# GPRSshield_V2.net
KiCad netlist of a schematic drawn in EAGLE
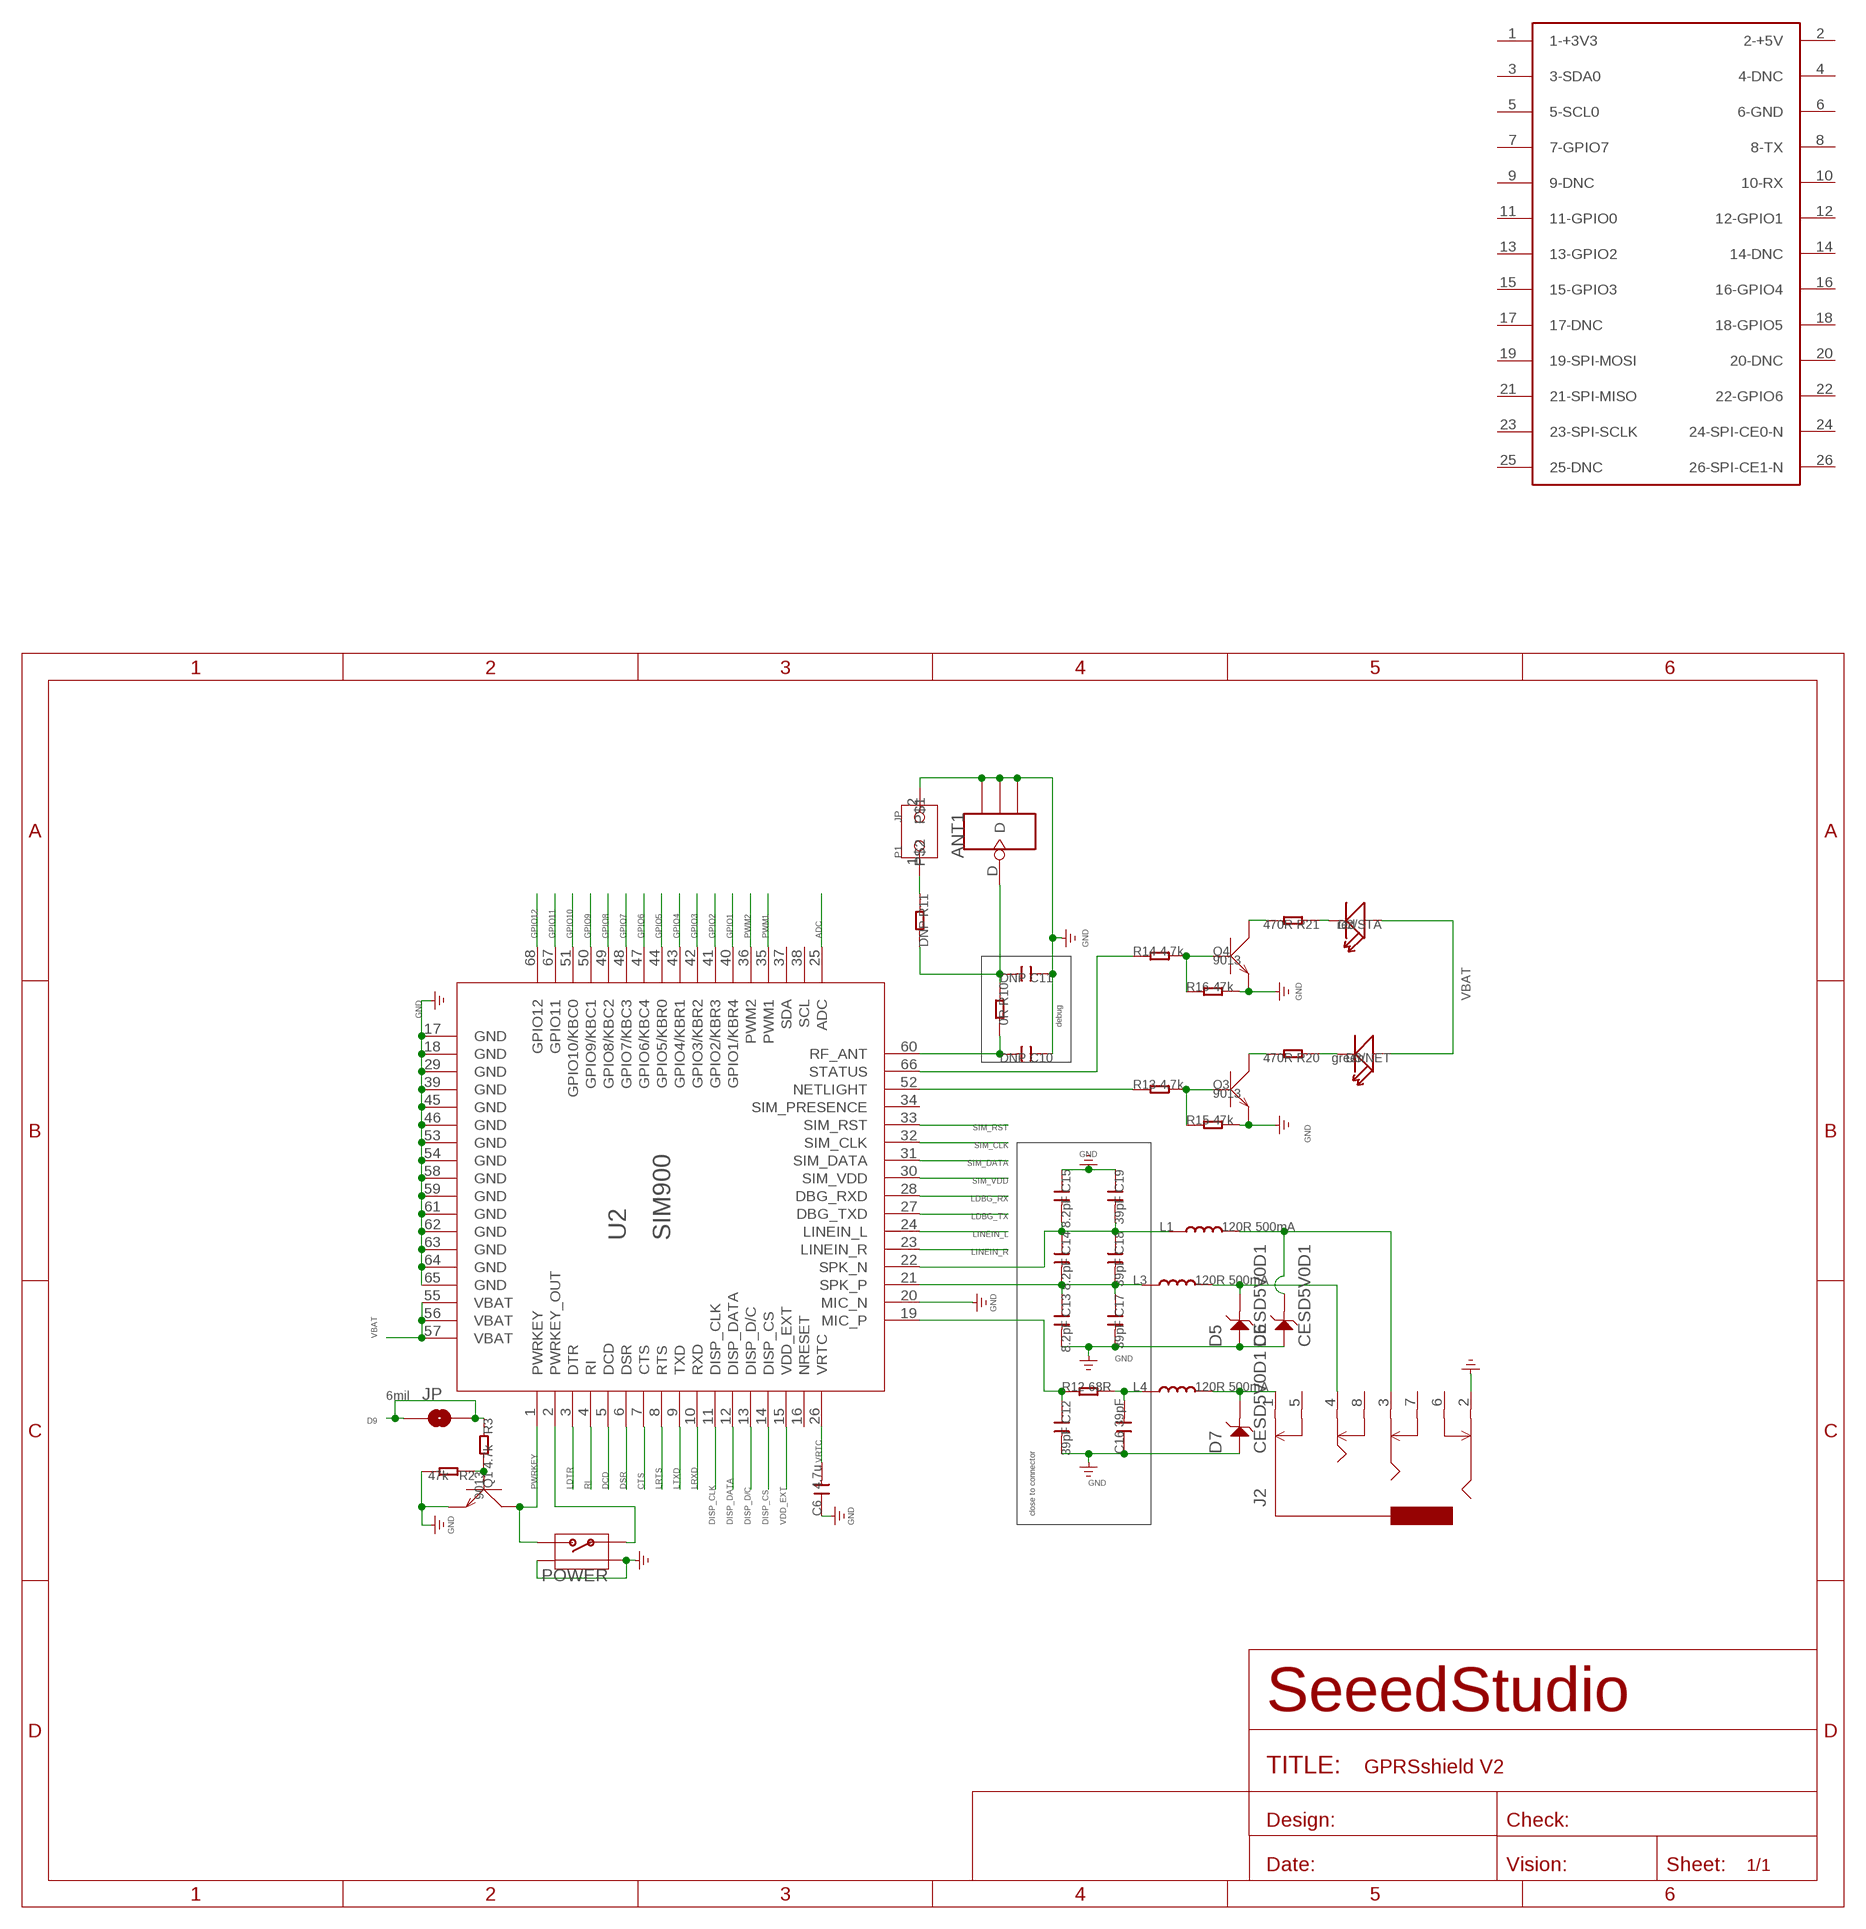
[diagram p0: schematic, sheet 1, part 1 of 2]
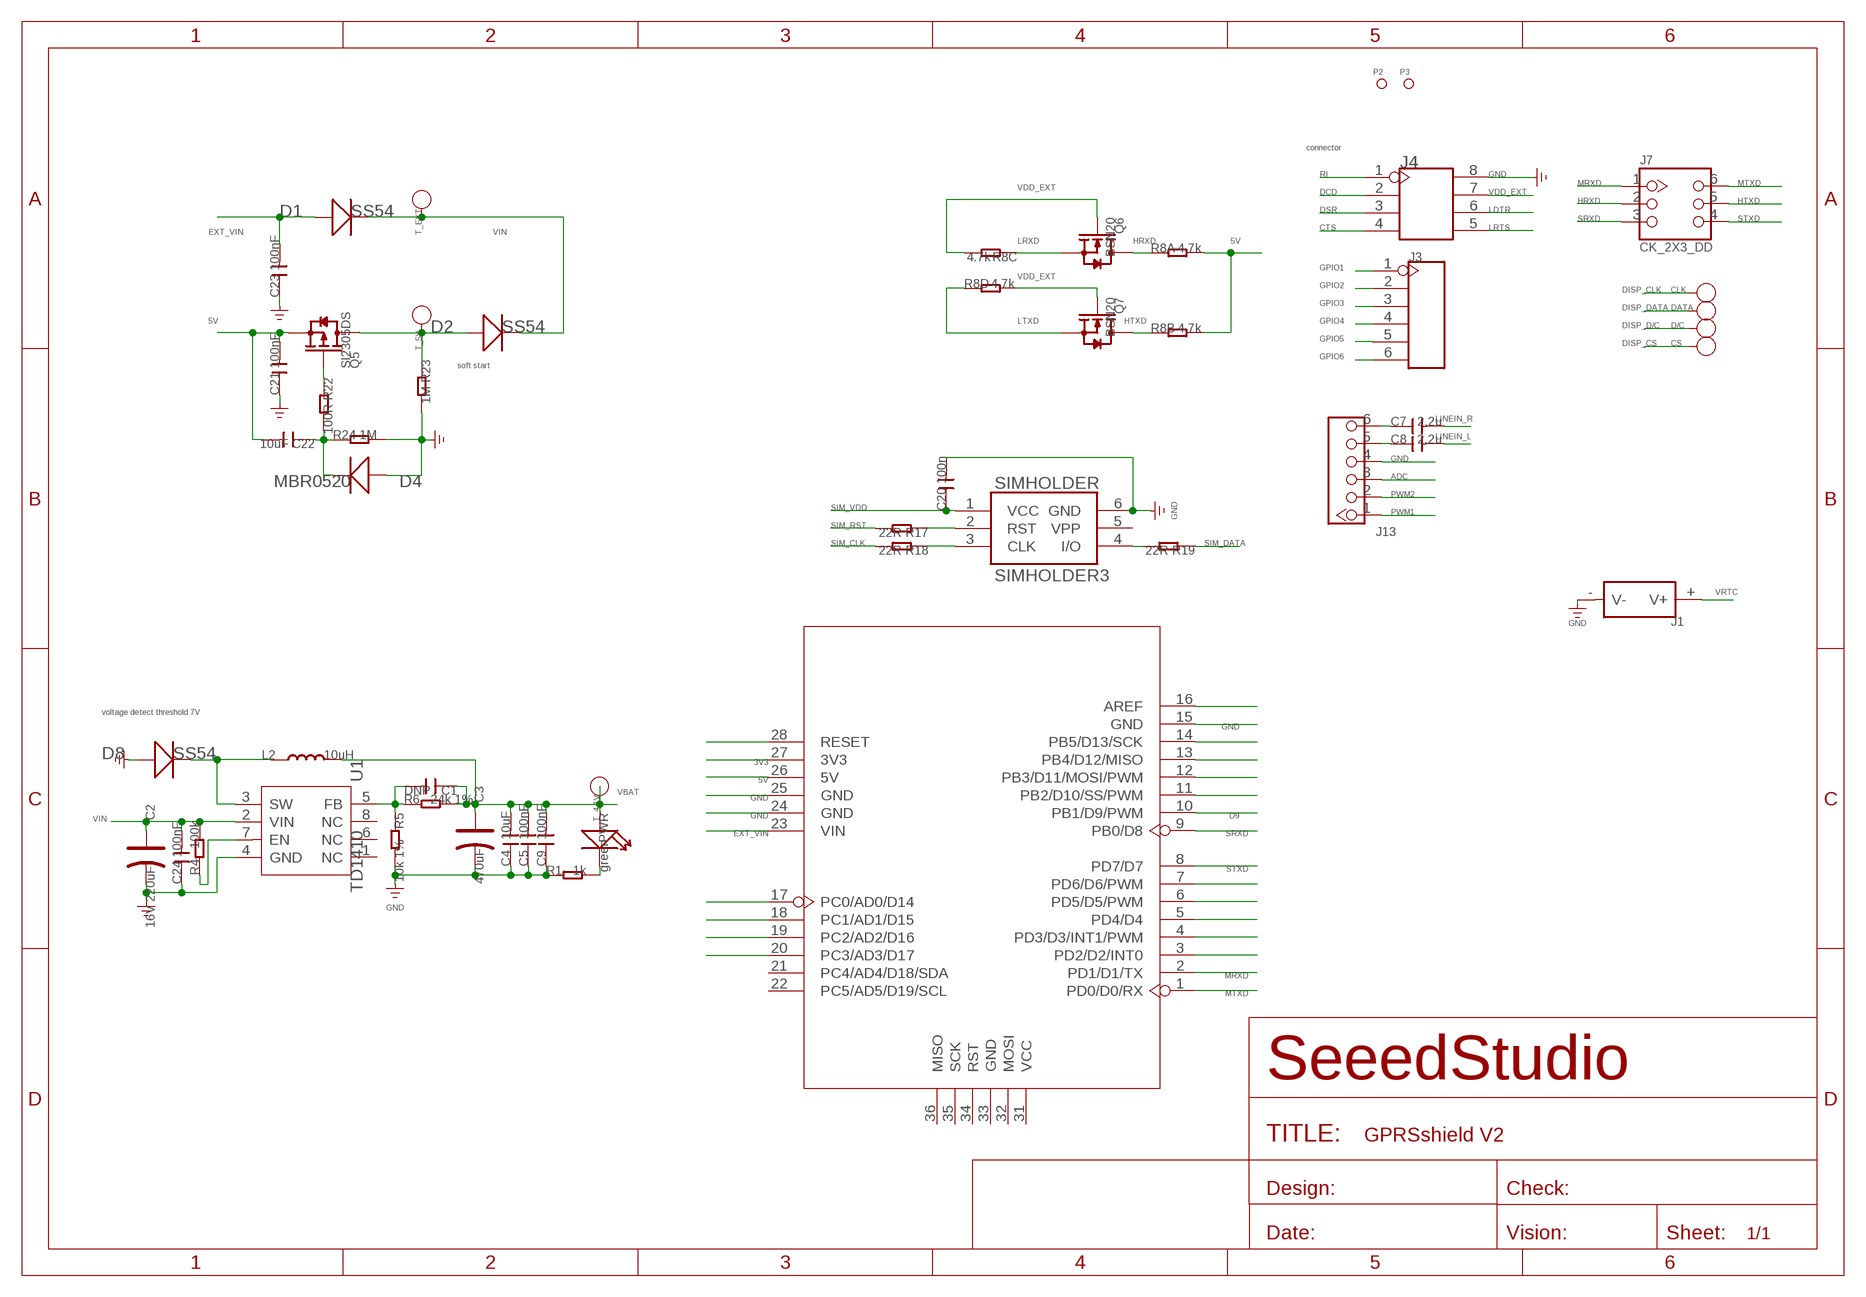
[diagram p1: schematic, sheet 1, part 2 of 2]

(export (version "E")
  (design (tool "Eeschema 10.0.6"))
  (components
    (comp (ref "ANT1")
      (value "ANTENNA-U-FL")
      (footprint "eagle-import:4P-U-FL")
      (libsource (lib "eagle-import") (part "ANTENNA-U-FL"))
    )
    (comp (ref "C1")
      (value "DNP")
      (footprint "eagle-import:C0603")
      (libsource (lib "eagle-import") (part "C-0603"))
    )
    (comp (ref "C2")
      (value "16V 220uF")
      (footprint "eagle-import:ELECTRO-SMD-D-5.6MM")
      (libsource (lib "eagle-import") (part "CAP-ELECTRO-D"))
    )
    (comp (ref "C3")
      (value "470uF")
      (footprint "eagle-import:AVX-D")
      (libsource (lib "eagle-import") (part "CAP-AVX-D"))
    )
    (comp (ref "C4")
      (value "10uF")
      (footprint "eagle-import:C0805")
      (libsource (lib "eagle-import") (part "C-0805"))
    )
    (comp (ref "C5")
      (value "100nF")
      (footprint "eagle-import:C0603")
      (libsource (lib "eagle-import") (part "C-0603"))
    )
    (comp (ref "C6")
      (value "4.7u")
      (footprint "eagle-import:C0805")
      (libsource (lib "eagle-import") (part "C-0805"))
    )
    (comp (ref "C7")
      (value "2.2u")
      (footprint "eagle-import:C0805")
      (libsource (lib "eagle-import") (part "C-0805"))
    )
    (comp (ref "C8")
      (value "2.2u")
      (footprint "eagle-import:C0805")
      (libsource (lib "eagle-import") (part "C-0805"))
    )
    (comp (ref "C9")
      (value "100nF")
      (footprint "eagle-import:C0603")
      (libsource (lib "eagle-import") (part "C-0603"))
    )
    (comp (ref "C10")
      (value "DNP")
      (footprint "eagle-import:C0603")
      (libsource (lib "eagle-import") (part "C-0603"))
    )
    (comp (ref "C11")
      (value "DNP")
      (footprint "eagle-import:C0603")
      (libsource (lib "eagle-import") (part "C-0603"))
    )
    (comp (ref "C12")
      (value "39pF")
      (footprint "eagle-import:C0603")
      (libsource (lib "eagle-import") (part "C-0603"))
    )
    (comp (ref "C13")
      (value "8.2pF")
      (footprint "eagle-import:C0603")
      (libsource (lib "eagle-import") (part "C-0603"))
    )
    (comp (ref "C14")
      (value "8.2pF")
      (footprint "eagle-import:C0603")
      (libsource (lib "eagle-import") (part "C-0603"))
    )
    (comp (ref "C15")
      (value "8.2pF")
      (footprint "eagle-import:C0603")
      (libsource (lib "eagle-import") (part "C-0603"))
    )
    (comp (ref "C16")
      (value "39pF")
      (footprint "eagle-import:C0603")
      (libsource (lib "eagle-import") (part "C-0603"))
    )
    (comp (ref "C17")
      (value "39pF")
      (footprint "eagle-import:C0603")
      (libsource (lib "eagle-import") (part "C-0603"))
    )
    (comp (ref "C18")
      (value "39pF")
      (footprint "eagle-import:C0603")
      (libsource (lib "eagle-import") (part "C-0603"))
    )
    (comp (ref "C19")
      (value "39pF")
      (footprint "eagle-import:C0603")
      (libsource (lib "eagle-import") (part "C-0603"))
    )
    (comp (ref "C20")
      (value "100n")
      (footprint "eagle-import:C0603")
      (libsource (lib "eagle-import") (part "C-0603"))
    )
    (comp (ref "C21")
      (value "100nF")
      (footprint "eagle-import:C0603")
      (libsource (lib "eagle-import") (part "C-0603"))
    )
    (comp (ref "C22")
      (value "10uF")
      (footprint "eagle-import:C0805")
      (libsource (lib "eagle-import") (part "C-0805"))
    )
    (comp (ref "C23")
      (value "100nF")
      (footprint "eagle-import:C0603")
      (libsource (lib "eagle-import") (part "C-0603"))
    )
    (comp (ref "C24")
      (value "100nF")
      (footprint "eagle-import:C0603")
      (libsource (lib "eagle-import") (part "C-0603"))
    )
    (comp (ref "CLK")
      (value "PAD-TEST-POINT-CIRCLE'4545'")
      (footprint "eagle-import:TP_4545")
      (fields (field (name "PARTNO") "DNP"))
      (libsource (lib "eagle-import") (part "PAD-TEST-POINT-CIRCLE'4545'"))
    )
    (comp (ref "CS")
      (value "PAD-TEST-POINT-CIRCLE'4545'")
      (footprint "eagle-import:TP_4545")
      (fields (field (name "PARTNO") "DNP"))
      (libsource (lib "eagle-import") (part "PAD-TEST-POINT-CIRCLE'4545'"))
    )
    (comp (ref "D/C")
      (value "PAD-TEST-POINT-CIRCLE'4545'")
      (footprint "eagle-import:TP_4545")
      (fields (field (name "PARTNO") "DNP"))
      (libsource (lib "eagle-import") (part "PAD-TEST-POINT-CIRCLE'4545'"))
    )
    (comp (ref "D1")
      (value "SS54")
      (footprint "eagle-import:SMB")
      (libsource (lib "eagle-import") (part "D'MBRS240LT3'"))
    )
    (comp (ref "D2")
      (value "SS54")
      (footprint "eagle-import:SMB")
      (libsource (lib "eagle-import") (part "D'MBRS240LT3'"))
    )
    (comp (ref "D2/STA")
      (value "red")
      (footprint "eagle-import:LED-0603")
      (libsource (lib "eagle-import") (part "LED'0603'"))
    )
    (comp (ref "D3/NET")
      (value "green")
      (footprint "eagle-import:LED-0603")
      (libsource (lib "eagle-import") (part "LED'0603'"))
    )
    (comp (ref "D4")
      (value "MBR0520")
      (footprint "eagle-import:SOD123-2.7X1.6")
      (libsource (lib "eagle-import") (part "D'MBR0520LT1'"))
    )
    (comp (ref "D5")
      (value "CESD5V0D1")
      (footprint "eagle-import:SOD123-2.7X1.6")
      (libsource (lib "eagle-import") (part "D-ESD"))
    )
    (comp (ref "D6")
      (value "CESD5V0D1")
      (footprint "eagle-import:SOD123-2.7X1.6")
      (libsource (lib "eagle-import") (part "D-ESD"))
    )
    (comp (ref "D7")
      (value "CESD5V0D1")
      (footprint "eagle-import:SOD123-2.7X1.6")
      (libsource (lib "eagle-import") (part "D-ESD"))
    )
    (comp (ref "D8")
      (value "SS54")
      (footprint "eagle-import:SMB")
      (libsource (lib "eagle-import") (part "D'MBRS240LT3'"))
    )
    (comp (ref "DATA")
      (value "PAD-TEST-POINT-CIRCLE'4545'")
      (footprint "eagle-import:TP_4545")
      (fields (field (name "PARTNO") "DNP"))
      (libsource (lib "eagle-import") (part "PAD-TEST-POINT-CIRCLE'4545'"))
    )
    (comp (ref "J1")
      (value "HOLDER-BAT")
      (footprint "eagle-import:SMD-CR1220-2")
      (libsource (lib "eagle-import") (part "HOLDER-BAT"))
    )
    (comp (ref "J2")
      (value "AUDIO-8P'PJ-3536-L6S'")
      (footprint "eagle-import:8P-3.5-SMD")
      (libsource (lib "eagle-import") (part "AUDIO-8P'PJ-3536-L6S'"))
    )
    (comp (ref "J3")
      (value "HEADER-6P-65/35MIL")
      (footprint "eagle-import:6P-2.54-65_35MIL")
      (libsource (lib "eagle-import") (part "HEADER-6P-65/35MIL"))
    )
    (comp (ref "J4")
      (value "HEADER-2X4P-2.54")
      (footprint "eagle-import:2X4P-2.54")
      (libsource (lib "eagle-import") (part "HEADER-2X4P-2.54"))
    )
    (comp (ref "J7")
      (value "CK_2X3_DD")
      (footprint "eagle-import:CK_2X3")
      (libsource (lib "eagle-import") (part "CK_2X3_DD"))
    )
    (comp (ref "J13")
      (value "HEADER_1X6")
      (footprint "eagle-import:CK_1X6")
      (libsource (lib "eagle-import") (part "HEADER_1X6"))
    )
    (comp (ref "JP")
      (value "PAD-SOLDERJUMPERNC")
      (footprint "eagle-import:2P-SMD-3.3X2")
      (libsource (lib "eagle-import") (part "PAD-SOLDERJUMPERNC"))
    )
    (comp (ref "L1")
      (value "120R 500mA")
      (footprint "eagle-import:L0603")
      (libsource (lib "eagle-import") (part "L'0603'"))
    )
    (comp (ref "L2")
      (value "10uH")
      (footprint "eagle-import:L0630")
      (libsource (lib "eagle-import") (part "L'0630'"))
    )
    (comp (ref "L3")
      (value "120R 500mA")
      (footprint "eagle-import:L0603")
      (libsource (lib "eagle-import") (part "L'0603'"))
    )
    (comp (ref "L4")
      (value "120R 500mA")
      (footprint "eagle-import:L0603")
      (libsource (lib "eagle-import") (part "L'0603'"))
    )
    (comp (ref "P1") (value "JP") (footprint "eagle-import:JP") (libsource (lib "eagle-import") (part "JP")))
    (comp (ref "P2")
      (value "PAD-MARK")
      (footprint "eagle-import:ROUND-MARK-1.0")
      (fields (field (name "PARTNO") "DNP"))
      (libsource (lib "eagle-import") (part "PAD-MARK"))
    )
    (comp (ref "P3")
      (value "PAD-MARK")
      (footprint "eagle-import:ROUND-MARK-1.0")
      (fields (field (name "PARTNO") "DNP"))
      (libsource (lib "eagle-import") (part "PAD-MARK"))
    )
    (comp (ref "POWER")
      (value "BUTTON-4P-REINFORCE'TS-118E'")
      (footprint "eagle-import:4P-SMD-7X3.5X3.5H")
      (libsource (lib "eagle-import") (part "BUTTON-4P-REINFORCE'TS-118E'"))
    )
    (comp (ref "PWR")
      (value "green")
      (footprint "eagle-import:D0603")
      (libsource (lib "eagle-import") (part "007-LED0603"))
    )
    (comp (ref "Q1")
      (value "9013")
      (footprint "eagle-import:SOT23")
      (libsource (lib "eagle-import") (part "TRANSISTOR-NPN-SOT23"))
    )
    (comp (ref "Q3")
      (value "9013")
      (footprint "eagle-import:SOT23")
      (libsource (lib "eagle-import") (part "TRANSISTOR-NPN-SOT23"))
    )
    (comp (ref "Q4")
      (value "9013")
      (footprint "eagle-import:SOT23")
      (libsource (lib "eagle-import") (part "TRANSISTOR-NPN-SOT23"))
    )
    (comp (ref "Q5")
      (value "SI2305DS")
      (footprint "eagle-import:SOT23")
      (libsource (lib "eagle-import") (part "MOSFET-P'SI2323CDS/SI2305DS{lt}BR{gt}'"))
    )
    (comp (ref "Q6")
      (value "BSN20")
      (footprint "eagle-import:SOT23")
      (libsource (lib "eagle-import") (part "MOSFET-N'SOT23'"))
    )
    (comp (ref "Q7")
      (value "BSN20")
      (footprint "eagle-import:SOT23")
      (libsource (lib "eagle-import") (part "MOSFET-N'SOT23'"))
    )
    (comp (ref "R1")
      (value "1k")
      (footprint "eagle-import:R0603")
      (libsource (lib "eagle-import") (part "R-0603"))
    )
    (comp (ref "R2")
      (value "47k")
      (footprint "eagle-import:R0603")
      (libsource (lib "eagle-import") (part "R-0603"))
    )
    (comp (ref "R3")
      (value "4.7k")
      (footprint "eagle-import:R0603")
      (libsource (lib "eagle-import") (part "R-0603"))
    )
    (comp (ref "R4")
      (value "100k")
      (footprint "eagle-import:R0603")
      (libsource (lib "eagle-import") (part "R-0603"))
    )
    (comp (ref "R5")
      (value "10k 1%")
      (footprint "eagle-import:R0603")
      (libsource (lib "eagle-import") (part "R-0603"))
    )
    (comp (ref "R6")
      (value "24k 1%")
      (footprint "eagle-import:R0603")
      (libsource (lib "eagle-import") (part "R-0603"))
    )
    (comp (ref "R8")
      (value "4.7k")
      (footprint "eagle-import:1206-8-3.3X2.4")
      (libsource (lib "eagle-import") (part "R-4R-1206"))
    )
    (comp (ref "R10")
      (value "0R")
      (footprint "eagle-import:R0603")
      (libsource (lib "eagle-import") (part "R-0603"))
    )
    (comp (ref "R11")
      (value "DNP")
      (footprint "eagle-import:R0603")
      (libsource (lib "eagle-import") (part "R-0603"))
    )
    (comp (ref "R12")
      (value "68R")
      (footprint "eagle-import:R0603")
      (libsource (lib "eagle-import") (part "R-0603"))
    )
    (comp (ref "R13")
      (value "4.7k")
      (footprint "eagle-import:R0603")
      (libsource (lib "eagle-import") (part "R-0603"))
    )
    (comp (ref "R14")
      (value "4.7k")
      (footprint "eagle-import:R0603")
      (libsource (lib "eagle-import") (part "R-0603"))
    )
    (comp (ref "R15")
      (value "47k")
      (footprint "eagle-import:R0603")
      (libsource (lib "eagle-import") (part "R-0603"))
    )
    (comp (ref "R16")
      (value "47k")
      (footprint "eagle-import:R0603")
      (libsource (lib "eagle-import") (part "R-0603"))
    )
    (comp (ref "R17")
      (value "22R")
      (footprint "eagle-import:R0603")
      (libsource (lib "eagle-import") (part "R-0603"))
    )
    (comp (ref "R18")
      (value "22R")
      (footprint "eagle-import:R0603")
      (libsource (lib "eagle-import") (part "R-0603"))
    )
    (comp (ref "R19")
      (value "22R")
      (footprint "eagle-import:R0603")
      (libsource (lib "eagle-import") (part "R-0603"))
    )
    (comp (ref "R20")
      (value "470R")
      (footprint "eagle-import:R0603")
      (libsource (lib "eagle-import") (part "R-0603"))
    )
    (comp (ref "R21")
      (value "470R")
      (footprint "eagle-import:R0603")
      (libsource (lib "eagle-import") (part "R-0603"))
    )
    (comp (ref "R22")
      (value "100R")
      (footprint "eagle-import:R0603")
      (libsource (lib "eagle-import") (part "R-0603"))
    )
    (comp (ref "R23")
      (value "1M")
      (footprint "eagle-import:R0603")
      (libsource (lib "eagle-import") (part "R-0603"))
    )
    (comp (ref "R24")
      (value "1M")
      (footprint "eagle-import:R0603")
      (libsource (lib "eagle-import") (part "R-0603"))
    )
    (comp (ref "SIMHOLDER")
      (value "SIMHOLDER3")
      (footprint "eagle-import:SIMHOLDER3")
      (libsource (lib "eagle-import") (part "SIMHOLDER3"))
    )
    (comp (ref "T_4.1V")
      (value "PAD-TEST-POINT-CIRCLE'4545'")
      (footprint "eagle-import:TP_4545")
      (fields (field (name "PARTNO") "DNP") (field (name "PARTNO_1") "DNP"))
      (libsource (lib "eagle-import") (part "PAD-TEST-POINT-CIRCLE'4545'"))
    )
    (comp (ref "T_5V")
      (value "PAD-TEST-POINT-CIRCLE'4545'")
      (footprint "eagle-import:TP_4545")
      (fields (field (name "PARTNO") "DNP") (field (name "PARTNO_1") "DNP"))
      (libsource (lib "eagle-import") (part "PAD-TEST-POINT-CIRCLE'4545'"))
    )
    (comp (ref "T_EXT")
      (value "PAD-TEST-POINT-CIRCLE'4545'")
      (footprint "eagle-import:TP_4545")
      (fields (field (name "PARTNO") "DNP") (field (name "PARTNO_1") "DNP"))
      (libsource (lib "eagle-import") (part "PAD-TEST-POINT-CIRCLE'4545'"))
    )
    (comp (ref "U$4")
      (value "RASPBERRY-PI")
      (footprint "eagle-import:RASPBERRY-PI")
      (libsource (lib "eagle-import") (part "RASPBERRY-PI"))
    )
    (comp (ref "U1")
      (value "TD1410")
      (footprint "eagle-import:SOP8")
      (libsource (lib "eagle-import") (part "TD1410"))
    )
    (comp (ref "U2")
      (value "SIM900")
      (footprint "eagle-import:SIM900")
      (libsource (lib "eagle-import") (part "SIM900"))
    )
    (comp (ref "U3")
      (value "ARDUINO'W/O-SILK'")
      (footprint "eagle-import:ARDUINO-W_O-SILK")
      (libsource (lib "eagle-import") (part "ARDUINO'W/O-SILK'"))
    )
  )
  (nets
    (net (code "1") (name "/3V3") (class "Default")
      (node (ref "U3") (pin "27") (pinfunction "3V3_27") (pintype "bidirectional"))
    )
    (net (code "2") (name "/5V") (class "Default")
      (node (ref "C21") (pin "2") (pinfunction "2_2") (pintype "passive"))
      (node (ref "C22") (pin "2") (pinfunction "2_2") (pintype "passive"))
      (node (ref "Q5") (pin "2") (pinfunction "S_2") (pintype "passive"))
      (node (ref "R8") (pin "7") (pinfunction "2_7") (pintype "passive"))
      (node (ref "R8") (pin "8") (pinfunction "2_8") (pintype "passive"))
      (node (ref "U3") (pin "26") (pinfunction "5V_26") (pintype "bidirectional"))
    )
    (net (code "3") (name "/ADC") (class "Default")
      (node (ref "J13") (pin "3") (pinfunction "3_3") (pintype "bidirectional"))
      (node (ref "U2") (pin "25") (pinfunction "ADC_25") (pintype "input"))
    )
    (net (code "4") (name "/CTS") (class "Default")
      (node (ref "J4") (pin "4") (pinfunction "4_4") (pintype "bidirectional"))
      (node (ref "U2") (pin "7") (pinfunction "CTS_7") (pintype "output"))
    )
    (net (code "5") (name "/D9") (class "Default")
      (node (ref "JP") (pin "1") (pinfunction "1_1") (pintype "passive"))
      (node (ref "JP") (pin "2") (pinfunction "2_2") (pintype "passive"))
      (node (ref "R3") (pin "1") (pinfunction "1_1") (pintype "passive"))
      (node (ref "U3") (pin "10") (pinfunction "PB1/D9/PWM_10") (pintype "bidirectional"))
    )
    (net (code "6") (name "/DCD") (class "Default")
      (node (ref "J4") (pin "2") (pinfunction "2_2") (pintype "bidirectional"))
      (node (ref "U2") (pin "5") (pinfunction "DCD_5") (pintype "output"))
    )
    (net (code "7") (name "/DISP_CLK") (class "Default")
      (node (ref "CLK") (pin "T") (pinfunction "T_T") (pintype "bidirectional"))
      (node (ref "U2") (pin "11") (pinfunction "DISP_CLK_11") (pintype "output"))
    )
    (net (code "8") (name "/DISP_CS") (class "Default")
      (node (ref "CS") (pin "T") (pinfunction "T_T") (pintype "bidirectional"))
      (node (ref "U2") (pin "14") (pinfunction "DISP_CS_14") (pintype "output"))
    )
    (net (code "9") (name "/DISP_DATA") (class "Default")
      (node (ref "DATA") (pin "T") (pinfunction "T_T") (pintype "bidirectional"))
      (node (ref "U2") (pin "12") (pinfunction "DISP_DATA_12") (pintype "bidirectional"))
    )
    (net (code "10") (name "/DISP_D{slash}C") (class "Default")
      (node (ref "D/C") (pin "T") (pinfunction "T_T") (pintype "bidirectional"))
      (node (ref "U2") (pin "13") (pinfunction "DISP_D/C_13") (pintype "output"))
    )
    (net (code "11") (name "/DSR") (class "Default")
      (node (ref "J4") (pin "3") (pinfunction "3_3") (pintype "bidirectional"))
      (node (ref "U2") (pin "6") (pinfunction "DSR_6") (pintype "output"))
    )
    (net (code "12") (name "/EXT_VIN") (class "Default")
      (node (ref "C23") (pin "2") (pinfunction "2_2") (pintype "passive"))
      (node (ref "D1") (pin "+") (pinfunction "+_+") (pintype "passive"))
      (node (ref "U3") (pin "23") (pinfunction "VIN_23") (pintype "bidirectional"))
    )
    (net (code "13") (name "/GPIO1") (class "Default")
      (node (ref "J3") (pin "1") (pinfunction "1_1") (pintype "bidirectional"))
      (node (ref "U2") (pin "40") (pinfunction "GPIO1/KBR4_40") (pintype "output"))
    )
    (net (code "14") (name "/GPIO2") (class "Default")
      (node (ref "J3") (pin "2") (pinfunction "2_2") (pintype "bidirectional"))
      (node (ref "U2") (pin "41") (pinfunction "GPIO2/KBR3_41") (pintype "output"))
    )
    (net (code "15") (name "/GPIO3") (class "Default")
      (node (ref "J3") (pin "3") (pinfunction "3_3") (pintype "bidirectional"))
      (node (ref "U2") (pin "42") (pinfunction "GPIO3/KBR2_42") (pintype "output"))
    )
    (net (code "16") (name "/GPIO4") (class "Default")
      (node (ref "J3") (pin "4") (pinfunction "4_4") (pintype "bidirectional"))
      (node (ref "U2") (pin "43") (pinfunction "GPIO4/KBR1_43") (pintype "output"))
    )
    (net (code "17") (name "/GPIO5") (class "Default")
      (node (ref "J3") (pin "5") (pinfunction "5_5") (pintype "bidirectional"))
      (node (ref "U2") (pin "44") (pinfunction "GPIO5/KBR0_44") (pintype "output"))
    )
    (net (code "18") (name "/GPIO6") (class "Default")
      (node (ref "J3") (pin "6") (pinfunction "6_6") (pintype "bidirectional"))
      (node (ref "U2") (pin "47") (pinfunction "GPIO6/KBC4_47") (pintype "input"))
    )
    (net (code "19") (name "/GPIO7") (class "Default")
      (node (ref "U2") (pin "48") (pinfunction "GPIO7/KBC3_48") (pintype "bidirectional"))
    )
    (net (code "20") (name "/GPIO8") (class "Default")
      (node (ref "U2") (pin "49") (pinfunction "GPIO8/KBC2_49") (pintype "input"))
    )
    (net (code "21") (name "/GPIO9") (class "Default")
      (node (ref "U2") (pin "50") (pinfunction "GPIO9/KBC1_50") (pintype "input"))
    )
    (net (code "22") (name "/GPIO10") (class "Default")
      (node (ref "U2") (pin "51") (pinfunction "GPIO10/KBC0_51") (pintype "bidirectional"))
    )
    (net (code "23") (name "/GPIO11") (class "Default")
      (node (ref "U2") (pin "67") (pinfunction "GPIO11_67") (pintype "bidirectional"))
    )
    (net (code "24") (name "/GPIO12") (class "Default")
      (node (ref "U2") (pin "68") (pinfunction "GPIO12_68") (pintype "bidirectional"))
    )
    (net (code "25") (name "/HRXD") (class "Default")
      (node (ref "J7") (pin "2") (pinfunction "2_2") (pintype "bidirectional"))
      (node (ref "Q6") (pin "3") (pinfunction "D_3") (pintype "passive"))
      (node (ref "R8") (pin "1") (pinfunction "1_1") (pintype "passive"))
    )
    (net (code "26") (name "/HTXD") (class "Default")
      (node (ref "J7") (pin "5") (pinfunction "5_5") (pintype "bidirectional"))
      (node (ref "Q7") (pin "3") (pinfunction "D_3") (pintype "passive"))
      (node (ref "R8") (pin "2") (pinfunction "1_2") (pintype "passive"))
    )
    (net (code "27") (name "/LDBG_RX") (class "Default")
      (node (ref "U2") (pin "28") (pinfunction "DBG_RXD_28") (pintype "input"))
    )
    (net (code "28") (name "/LDBG_TX") (class "Default")
      (node (ref "U2") (pin "27") (pinfunction "DBG_TXD_27") (pintype "output"))
    )
    (net (code "29") (name "/LDTR") (class "Default")
      (node (ref "J4") (pin "6") (pinfunction "6_6") (pintype "bidirectional"))
      (node (ref "U2") (pin "3") (pinfunction "DTR_3") (pintype "input"))
    )
    (net (code "30") (name "/LINEIN_L") (class "Default")
      (node (ref "C8") (pin "2") (pinfunction "2_2") (pintype "passive"))
      (node (ref "U2") (pin "24") (pinfunction "LINEIN_L_24") (pintype "input"))
    )
    (net (code "31") (name "/LINEIN_R") (class "Default")
      (node (ref "C7") (pin "2") (pinfunction "2_2") (pintype "passive"))
      (node (ref "U2") (pin "23") (pinfunction "LINEIN_R_23") (pintype "input"))
    )
    (net (code "32") (name "/LRTS") (class "Default")
      (node (ref "J4") (pin "5") (pinfunction "5_5") (pintype "bidirectional"))
      (node (ref "U2") (pin "8") (pinfunction "RTS_8") (pintype "input"))
    )
    (net (code "33") (name "/LRXD") (class "Default")
      (node (ref "Q6") (pin "2") (pinfunction "S_2") (pintype "passive"))
      (node (ref "R8") (pin "3") (pinfunction "1_3") (pintype "passive"))
      (node (ref "U2") (pin "10") (pinfunction "RXD_10") (pintype "input"))
    )
    (net (code "34") (name "/LTXD") (class "Default")
      (node (ref "Q7") (pin "2") (pinfunction "S_2") (pintype "passive"))
      (node (ref "R8") (pin "4") (pinfunction "1_4") (pintype "passive"))
      (node (ref "U2") (pin "9") (pinfunction "TXD_9") (pintype "output"))
    )
    (net (code "35") (name "/MRXD") (class "Default")
      (node (ref "J7") (pin "1") (pinfunction "1_1") (pintype "bidirectional"))
      (node (ref "U3") (pin "2") (pinfunction "PD1/D1/TX_2") (pintype "bidirectional"))
    )
    (net (code "36") (name "/MTXD") (class "Default")
      (node (ref "J7") (pin "6") (pinfunction "6_6") (pintype "bidirectional"))
      (node (ref "U3") (pin "1") (pinfunction "PD0/D0/RX_1") (pintype "bidirectional"))
    )
    (net (code "37") (name "/PWM1") (class "Default")
      (node (ref "J13") (pin "1") (pinfunction "1_1") (pintype "bidirectional"))
      (node (ref "U2") (pin "35") (pinfunction "PWM1_35") (pintype "output"))
    )
    (net (code "38") (name "/PWM2") (class "Default")
      (node (ref "J13") (pin "2") (pinfunction "2_2") (pintype "bidirectional"))
      (node (ref "U2") (pin "36") (pinfunction "PWM2_36") (pintype "output"))
    )
    (net (code "39") (name "/PWRKEY") (class "Default")
      (node (ref "POWER") (pin "2") (pinfunction "2_2") (pintype "bidirectional"))
      (node (ref "Q1") (pin "3") (pinfunction "C_3") (pintype "passive"))
      (node (ref "U2") (pin "1") (pinfunction "PWRKEY_1") (pintype "input"))
    )
    (net (code "40") (name "/RI") (class "Default")
      (node (ref "J4") (pin "1") (pinfunction "1_1") (pintype "bidirectional"))
      (node (ref "U2") (pin "4") (pinfunction "RI_4") (pintype "output"))
    )
    (net (code "41") (name "/SIM_CLK") (class "Default")
      (node (ref "R18") (pin "2") (pinfunction "2_2") (pintype "passive"))
      (node (ref "U2") (pin "32") (pinfunction "SIM_CLK_32") (pintype "output"))
    )
    (net (code "42") (name "/SIM_DATA") (class "Default")
      (node (ref "R19") (pin "1") (pinfunction "1_1") (pintype "passive"))
      (node (ref "U2") (pin "31") (pinfunction "SIM_DATA_31") (pintype "bidirectional"))
    )
    (net (code "43") (name "/SIM_RST") (class "Default")
      (node (ref "R17") (pin "2") (pinfunction "2_2") (pintype "passive"))
      (node (ref "U2") (pin "33") (pinfunction "SIM_RST_33") (pintype "output"))
    )
    (net (code "44") (name "/SIM_VDD") (class "Default")
      (node (ref "C20") (pin "1") (pinfunction "1_1") (pintype "passive"))
      (node (ref "SIMHOLDER") (pin "1") (pinfunction "VCC_1") (pintype "bidirectional"))
      (node (ref "U2") (pin "30") (pinfunction "SIM_VDD_30") (pintype "output"))
    )
    (net (code "45") (name "/SRXD") (class "Default")
      (node (ref "J7") (pin "3") (pinfunction "3_3") (pintype "bidirectional"))
      (node (ref "U3") (pin "9") (pinfunction "PB0/D8_9") (pintype "bidirectional"))
    )
    (net (code "46") (name "/STXD") (class "Default")
      (node (ref "J7") (pin "4") (pinfunction "4_4") (pintype "bidirectional"))
      (node (ref "U3") (pin "8") (pinfunction "PD7/D7_8") (pintype "bidirectional"))
    )
    (net (code "47") (name "/VBAT") (class "Default")
      (node (ref "C1") (pin "1") (pinfunction "1_1") (pintype "passive"))
      (node (ref "C3") (pin "+") (pinfunction "+_+") (pintype "passive"))
      (node (ref "C4") (pin "2") (pinfunction "2_2") (pintype "passive"))
      (node (ref "C5") (pin "2") (pinfunction "2_2") (pintype "passive"))
      (node (ref "C9") (pin "2") (pinfunction "2_2") (pintype "passive"))
      (node (ref "D2/STA") (pin "+") (pinfunction "+_+") (pintype "passive"))
      (node (ref "D3/NET") (pin "+") (pinfunction "+_+") (pintype "passive"))
      (node (ref "L2") (pin "2") (pinfunction "2_2") (pintype "passive"))
      (node (ref "PWR") (pin "+") (pinfunction "+_+") (pintype "passive"))
      (node (ref "R6") (pin "2") (pinfunction "2_2") (pintype "passive"))
      (node (ref "T_4.1V") (pin "T") (pinfunction "T_T") (pintype "bidirectional"))
      (node (ref "U2") (pin "55") (pinfunction "VBAT_55") (pintype "power_in"))
      (node (ref "U2") (pin "56") (pinfunction "VBAT_56") (pintype "power_in"))
      (node (ref "U2") (pin "57") (pinfunction "VBAT_57") (pintype "power_in"))
    )
    (net (code "48") (name "/VDD_EXT") (class "Default")
      (node (ref "J4") (pin "7") (pinfunction "7_7") (pintype "bidirectional"))
      (node (ref "Q6") (pin "1") (pinfunction "G_1") (pintype "passive"))
      (node (ref "Q7") (pin "1") (pinfunction "G_1") (pintype "passive"))
      (node (ref "R8") (pin "5") (pinfunction "2_5") (pintype "passive"))
      (node (ref "R8") (pin "6") (pinfunction "2_6") (pintype "passive"))
      (node (ref "U2") (pin "15") (pinfunction "VDD_EXT_15") (pintype "output"))
    )
    (net (code "49") (name "/VIN") (class "Default")
      (node (ref "C2") (pin "+") (pinfunction "+_+") (pintype "passive"))
      (node (ref "C24") (pin "2") (pinfunction "2_2") (pintype "passive"))
      (node (ref "D1") (pin "-") (pinfunction "-_-") (pintype "passive"))
      (node (ref "D2") (pin "-") (pinfunction "-_-") (pintype "passive"))
      (node (ref "R4") (pin "2") (pinfunction "2_2") (pintype "passive"))
      (node (ref "T_EXT") (pin "T") (pinfunction "T_T") (pintype "bidirectional"))
      (node (ref "U1") (pin "2") (pinfunction "VIN_2") (pintype "input"))
    )
    (net (code "50") (name "/VRTC") (class "Default")
      (node (ref "C6") (pin "2") (pinfunction "2_2") (pintype "passive"))
      (node (ref "J1") (pin "+") (pinfunction "V+_+") (pintype "bidirectional"))
      (node (ref "U2") (pin "26") (pinfunction "VRTC_26") (pintype "bidirectional"))
    )
    (net (code "51") (name "GND_POWER") (class "Default")
      (node (ref "ANT1") (pin "GND1") (pinfunction "GND1_GND1") (pintype "bidirectional"))
      (node (ref "ANT1") (pin "GND2") (pinfunction "GND2_GND2") (pintype "bidirectional"))
      (node (ref "ANT1") (pin "GND3") (pinfunction "GND3_GND3") (pintype "bidirectional"))
      (node (ref "C10") (pin "1") (pinfunction "1_1") (pintype "passive"))
      (node (ref "C11") (pin "1") (pinfunction "1_1") (pintype "passive"))
      (node (ref "C12") (pin "2") (pinfunction "2_2") (pintype "passive"))
      (node (ref "C13") (pin "2") (pinfunction "2_2") (pintype "passive"))
      (node (ref "C15") (pin "1") (pinfunction "1_1") (pintype "passive"))
      (node (ref "C16") (pin "1") (pinfunction "1_1") (pintype "passive"))
      (node (ref "C17") (pin "2") (pinfunction "2_2") (pintype "passive"))
      (node (ref "C19") (pin "1") (pinfunction "1_1") (pintype "passive"))
      (node (ref "C2") (pin "-") (pinfunction "-_-") (pintype "passive"))
      (node (ref "C20") (pin "2") (pinfunction "2_2") (pintype "passive"))
      (node (ref "C21") (pin "1") (pinfunction "1_1") (pintype "passive"))
      (node (ref "C23") (pin "1") (pinfunction "1_1") (pintype "passive"))
      (node (ref "C24") (pin "1") (pinfunction "1_1") (pintype "passive"))
      (node (ref "C3") (pin "-") (pinfunction "-_-") (pintype "passive"))
      (node (ref "C4") (pin "1") (pinfunction "1_1") (pintype "passive"))
      (node (ref "C5") (pin "1") (pinfunction "1_1") (pintype "passive"))
      (node (ref "C6") (pin "1") (pinfunction "1_1") (pintype "passive"))
      (node (ref "C9") (pin "1") (pinfunction "1_1") (pintype "passive"))
      (node (ref "D4") (pin "1") (pinfunction "+_1") (pintype "passive"))
      (node (ref "D5") (pin "1") (pinfunction "1_1") (pintype "bidirectional"))
      (node (ref "D6") (pin "1") (pinfunction "1_1") (pintype "bidirectional"))
      (node (ref "D7") (pin "1") (pinfunction "1_1") (pintype "bidirectional"))
      (node (ref "D8") (pin "+") (pinfunction "+_+") (pintype "passive"))
      (node (ref "J1") (pin "-") (pinfunction "V-_-") (pintype "bidirectional"))
      (node (ref "J13") (pin "4") (pinfunction "4_4") (pintype "bidirectional"))
      (node (ref "J2") (pin "2") (pinfunction "2_2") (pintype "bidirectional"))
      (node (ref "J4") (pin "8") (pinfunction "8_8") (pintype "bidirectional"))
      (node (ref "P1") (pin "2") (pinfunction "P$2_2") (pintype "bidirectional"))
      (node (ref "POWER") (pin "S1") (pinfunction "S1_S1") (pintype "bidirectional"))
      (node (ref "POWER") (pin "S2") (pinfunction "S2_S2") (pintype "bidirectional"))
      (node (ref "Q1") (pin "2") (pinfunction "E_2") (pintype "passive"))
      (node (ref "Q3") (pin "2") (pinfunction "E_2") (pintype "passive"))
      (node (ref "Q4") (pin "2") (pinfunction "E_2") (pintype "passive"))
      (node (ref "R1") (pin "1") (pinfunction "1_1") (pintype "passive"))
      (node (ref "R15") (pin "2") (pinfunction "2_2") (pintype "passive"))
      (node (ref "R16") (pin "2") (pinfunction "2_2") (pintype "passive"))
      (node (ref "R2") (pin "2") (pinfunction "2_2") (pintype "passive"))
      (node (ref "R23") (pin "2") (pinfunction "2_2") (pintype "passive"))
      (node (ref "R24") (pin "2") (pinfunction "2_2") (pintype "passive"))
      (node (ref "R5") (pin "2") (pinfunction "2_2") (pintype "passive"))
      (node (ref "SIMHOLDER") (pin "6") (pinfunction "GND_6") (pintype "bidirectional"))
      (node (ref "U1") (pin "4") (pinfunction "GND_4") (pintype "power_in"))
      (node (ref "U2") (pin "17") (pinfunction "GND_17") (pintype "power_in"))
      (node (ref "U2") (pin "18") (pinfunction "GND_18") (pintype "power_in"))
      (node (ref "U2") (pin "20") (pinfunction "MIC_N_20") (pintype "input"))
      (node (ref "U2") (pin "29") (pinfunction "GND_29") (pintype "power_in"))
      (node (ref "U2") (pin "39") (pinfunction "GND_39") (pintype "power_in"))
      (node (ref "U2") (pin "45") (pinfunction "GND_45") (pintype "power_in"))
      (node (ref "U2") (pin "46") (pinfunction "GND_46") (pintype "power_in"))
      (node (ref "U2") (pin "53") (pinfunction "GND_53") (pintype "power_in"))
      (node (ref "U2") (pin "54") (pinfunction "GND_54") (pintype "power_in"))
      (node (ref "U2") (pin "58") (pinfunction "GND_58") (pintype "power_in"))
      (node (ref "U2") (pin "59") (pinfunction "GND_59") (pintype "power_in"))
      (node (ref "U2") (pin "61") (pinfunction "GND_61") (pintype "power_in"))
      (node (ref "U2") (pin "62") (pinfunction "GND_62") (pintype "power_in"))
      (node (ref "U2") (pin "63") (pinfunction "GND_63") (pintype "power_in"))
      (node (ref "U2") (pin "64") (pinfunction "GND_64") (pintype "power_in"))
      (node (ref "U2") (pin "65") (pinfunction "GND_65") (pintype "power_in"))
      (node (ref "U3") (pin "15") (pinfunction "GND_15") (pintype "bidirectional"))
      (node (ref "U3") (pin "24") (pinfunction "GND_24") (pintype "bidirectional"))
      (node (ref "U3") (pin "25") (pinfunction "GND_25") (pintype "bidirectional"))
    )
    (net (code "52") (name "Net-(ANT1-PadD)") (class "Default")
      (node (ref "ANT1") (pin "D") (pinfunction "D_D") (pintype "bidirectional"))
      (node (ref "C11") (pin "2") (pinfunction "2_2") (pintype "passive"))
      (node (ref "R10") (pin "1") (pinfunction "1_1") (pintype "passive"))
      (node (ref "R11") (pin "2") (pinfunction "2_2") (pintype "passive"))
    )
    (net (code "53") (name "Net-(C7-Pad1)") (class "Default")
      (node (ref "C7") (pin "1") (pinfunction "1_1") (pintype "passive"))
      (node (ref "J13") (pin "6") (pinfunction "6_6") (pintype "bidirectional"))
    )
    (net (code "54") (name "Net-(C8-Pad1)") (class "Default")
      (node (ref "C8") (pin "1") (pinfunction "1_1") (pintype "passive"))
      (node (ref "J13") (pin "5") (pinfunction "5_5") (pintype "bidirectional"))
    )
    (net (code "55") (name "Net-(C16-Pad2)") (class "Default")
      (node (ref "C16") (pin "2") (pinfunction "2_2") (pintype "passive"))
      (node (ref "L4") (pin "1") (pinfunction "1_1") (pintype "passive"))
      (node (ref "R12") (pin "2") (pinfunction "2_2") (pintype "passive"))
    )
    (net (code "56") (name "Net-(D2/STA-Pad-)") (class "Default")
      (node (ref "D2/STA") (pin "-") (pinfunction "-_-") (pintype "passive"))
      (node (ref "R21") (pin "1") (pinfunction "1_1") (pintype "passive"))
    )
    (net (code "57") (name "Net-(D3/NET-Pad-)") (class "Default")
      (node (ref "D3/NET") (pin "-") (pinfunction "-_-") (pintype "passive"))
      (node (ref "R20") (pin "1") (pinfunction "1_1") (pintype "passive"))
    )
    (net (code "58") (name "Net-(D4--)") (class "Default")
      (node (ref "C22") (pin "1") (pinfunction "1_1") (pintype "passive"))
      (node (ref "D4") (pin "2") (pinfunction "-_2") (pintype "passive"))
      (node (ref "R22") (pin "2") (pinfunction "2_2") (pintype "passive"))
      (node (ref "R24") (pin "1") (pinfunction "1_1") (pintype "passive"))
    )
    (net (code "59") (name "Net-(D5-Pad2)") (class "Default")
      (node (ref "D5") (pin "2") (pinfunction "2_2") (pintype "bidirectional"))
      (node (ref "J2") (pin "4") (pinfunction "4_4") (pintype "bidirectional"))
      (node (ref "L3") (pin "2") (pinfunction "2_2") (pintype "passive"))
    )
    (net (code "60") (name "Net-(D6-Pad2)") (class "Default")
      (node (ref "D6") (pin "2") (pinfunction "2_2") (pintype "bidirectional"))
      (node (ref "J2") (pin "3") (pinfunction "3_3") (pintype "bidirectional"))
      (node (ref "L1") (pin "2") (pinfunction "2_2") (pintype "passive"))
    )
    (net (code "61") (name "Net-(D7-Pad2)") (class "Default")
      (node (ref "D7") (pin "2") (pinfunction "2_2") (pintype "bidirectional"))
      (node (ref "J2") (pin "1") (pinfunction "1_1") (pintype "bidirectional"))
      (node (ref "L4") (pin "2") (pinfunction "2_2") (pintype "passive"))
    )
    (net (code "62") (name "Net-(P1-P$1)") (class "Default")
      (node (ref "P1") (pin "1") (pinfunction "P$1_1") (pintype "bidirectional"))
      (node (ref "R11") (pin "1") (pinfunction "1_1") (pintype "passive"))
    )
    (net (code "63") (name "Net-(PWR-Pad-)") (class "Default")
      (node (ref "PWR") (pin "-") (pinfunction "-_-") (pintype "passive"))
      (node (ref "R1") (pin "2") (pinfunction "2_2") (pintype "passive"))
    )
    (net (code "64") (name "Net-(Q1-B)") (class "Default")
      (node (ref "Q1") (pin "1") (pinfunction "B_1") (pintype "passive"))
      (node (ref "R2") (pin "1") (pinfunction "1_1") (pintype "passive"))
      (node (ref "R3") (pin "2") (pinfunction "2_2") (pintype "passive"))
    )
    (net (code "65") (name "Net-(Q3-B)") (class "Default")
      (node (ref "Q3") (pin "1") (pinfunction "B_1") (pintype "passive"))
      (node (ref "R13") (pin "2") (pinfunction "2_2") (pintype "passive"))
      (node (ref "R15") (pin "1") (pinfunction "1_1") (pintype "passive"))
    )
    (net (code "66") (name "Net-(Q3-C)") (class "Default")
      (node (ref "Q3") (pin "3") (pinfunction "C_3") (pintype "passive"))
      (node (ref "R20") (pin "2") (pinfunction "2_2") (pintype "passive"))
    )
    (net (code "67") (name "Net-(Q4-B)") (class "Default")
      (node (ref "Q4") (pin "1") (pinfunction "B_1") (pintype "passive"))
      (node (ref "R14") (pin "2") (pinfunction "2_2") (pintype "passive"))
      (node (ref "R16") (pin "1") (pinfunction "1_1") (pintype "passive"))
    )
    (net (code "68") (name "Net-(Q4-C)") (class "Default")
      (node (ref "Q4") (pin "3") (pinfunction "C_3") (pintype "passive"))
      (node (ref "R21") (pin "2") (pinfunction "2_2") (pintype "passive"))
    )
    (net (code "69") (name "Net-(Q5-D)") (class "Default")
      (node (ref "D2") (pin "+") (pinfunction "+_+") (pintype "passive"))
      (node (ref "Q5") (pin "3") (pinfunction "D_3") (pintype "passive"))
      (node (ref "R23") (pin "1") (pinfunction "1_1") (pintype "passive"))
      (node (ref "T_5V") (pin "T") (pinfunction "T_T") (pintype "bidirectional"))
    )
    (net (code "70") (name "Net-(Q5-G)") (class "Default")
      (node (ref "Q5") (pin "1") (pinfunction "G_1") (pintype "passive"))
      (node (ref "R22") (pin "1") (pinfunction "1_1") (pintype "passive"))
    )
    (net (code "71") (name "Net-(SIMHOLDER-CLK)") (class "Default")
      (node (ref "R18") (pin "1") (pinfunction "1_1") (pintype "passive"))
      (node (ref "SIMHOLDER") (pin "3") (pinfunction "CLK_3") (pintype "bidirectional"))
    )
    (net (code "72") (name "Net-(SIMHOLDER-I{slash}O)") (class "Default")
      (node (ref "R19") (pin "2") (pinfunction "2_2") (pintype "passive"))
      (node (ref "SIMHOLDER") (pin "4") (pinfunction "I/O_4") (pintype "bidirectional"))
    )
    (net (code "73") (name "Net-(SIMHOLDER-RST)") (class "Default")
      (node (ref "R17") (pin "1") (pinfunction "1_1") (pintype "passive"))
      (node (ref "SIMHOLDER") (pin "2") (pinfunction "RST_2") (pintype "bidirectional"))
    )
    (net (code "74") (name "Net-(U1-EN)") (class "Default")
      (node (ref "R4") (pin "1") (pinfunction "1_1") (pintype "passive"))
      (node (ref "U1") (pin "7") (pinfunction "EN_7") (pintype "input"))
    )
    (net (code "75") (name "Net-(U1-FB)") (class "Default")
      (node (ref "C1") (pin "2") (pinfunction "2_2") (pintype "passive"))
      (node (ref "R5") (pin "1") (pinfunction "1_1") (pintype "passive"))
      (node (ref "R6") (pin "1") (pinfunction "1_1") (pintype "passive"))
      (node (ref "U1") (pin "5") (pinfunction "FB_5") (pintype "input"))
    )
    (net (code "76") (name "Net-(U1-SW)") (class "Default")
      (node (ref "D8") (pin "-") (pinfunction "-_-") (pintype "passive"))
      (node (ref "L2") (pin "1") (pinfunction "1_1") (pintype "passive"))
      (node (ref "U1") (pin "3") (pinfunction "SW_3") (pintype "output"))
    )
    (net (code "77") (name "Net-(U2-MIC_P)") (class "Default")
      (node (ref "C12") (pin "1") (pinfunction "1_1") (pintype "passive"))
      (node (ref "R12") (pin "1") (pinfunction "1_1") (pintype "passive"))
      (node (ref "U2") (pin "19") (pinfunction "MIC_P_19") (pintype "input"))
    )
    (net (code "78") (name "Net-(U2-NETLIGHT)") (class "Default")
      (node (ref "R13") (pin "1") (pinfunction "1_1") (pintype "passive"))
      (node (ref "U2") (pin "52") (pinfunction "NETLIGHT_52") (pintype "output"))
    )
    (net (code "79") (name "Net-(U2-PWRKEY_OUT)") (class "Default")
      (node (ref "POWER") (pin "1") (pinfunction "1_1") (pintype "bidirectional"))
      (node (ref "U2") (pin "2") (pinfunction "PWRKEY_OUT_2") (pintype "output"))
    )
    (net (code "80") (name "Net-(U2-RF_ANT)") (class "Default")
      (node (ref "C10") (pin "2") (pinfunction "2_2") (pintype "passive"))
      (node (ref "R10") (pin "2") (pinfunction "2_2") (pintype "passive"))
      (node (ref "U2") (pin "60") (pinfunction "RF_ANT_60") (pintype "bidirectional"))
    )
    (net (code "81") (name "Net-(U2-SPK_N)") (class "Default")
      (node (ref "C14") (pin "1") (pinfunction "1_1") (pintype "passive"))
      (node (ref "C15") (pin "2") (pinfunction "2_2") (pintype "passive"))
      (node (ref "C18") (pin "1") (pinfunction "1_1") (pintype "passive"))
      (node (ref "C19") (pin "2") (pinfunction "2_2") (pintype "passive"))
      (node (ref "L1") (pin "1") (pinfunction "1_1") (pintype "passive"))
      (node (ref "U2") (pin "22") (pinfunction "SPK_N_22") (pintype "output"))
    )
    (net (code "82") (name "Net-(U2-SPK_P)") (class "Default")
      (node (ref "C13") (pin "1") (pinfunction "1_1") (pintype "passive"))
      (node (ref "C14") (pin "2") (pinfunction "2_2") (pintype "passive"))
      (node (ref "C17") (pin "1") (pinfunction "1_1") (pintype "passive"))
      (node (ref "C18") (pin "2") (pinfunction "2_2") (pintype "passive"))
      (node (ref "L3") (pin "1") (pinfunction "1_1") (pintype "passive"))
      (node (ref "U2") (pin "21") (pinfunction "SPK_P_21") (pintype "output"))
    )
    (net (code "83") (name "Net-(U2-STATUS)") (class "Default")
      (node (ref "R14") (pin "1") (pinfunction "1_1") (pintype "passive"))
      (node (ref "U2") (pin "66") (pinfunction "STATUS_66") (pintype "output"))
    )
    (net (code "84") (name "unconnected-(J2-Pad5)") (class "Default")
      (node (ref "J2") (pin "5") (pinfunction "5_5") (pintype "bidirectional"))
    )
    (net (code "85") (name "unconnected-(J2-Pad6)") (class "Default")
      (node (ref "J2") (pin "6") (pinfunction "6_6") (pintype "bidirectional"))
    )
    (net (code "86") (name "unconnected-(J2-Pad7)") (class "Default")
      (node (ref "J2") (pin "7") (pinfunction "7_7") (pintype "bidirectional"))
    )
    (net (code "87") (name "unconnected-(J2-Pad8)") (class "Default")
      (node (ref "J2") (pin "8") (pinfunction "8_8") (pintype "bidirectional"))
    )
    (net (code "88") (name "unconnected-(SIMHOLDER-VPP-Pad5)") (class "Default")
      (node (ref "SIMHOLDER") (pin "5") (pinfunction "VPP_5") (pintype "bidirectional"))
    )
    (net (code "89") (name "unconnected-(U$4-1-+3V3-Pad1)") (class "Default")
      (node (ref "U$4") (pin "1") (pinfunction "1-+3V3_1") (pintype "bidirectional"))
    )
    (net (code "90") (name "unconnected-(U$4-2-+5V-Pad2)") (class "Default")
      (node (ref "U$4") (pin "2") (pinfunction "2-+5V_2") (pintype "bidirectional"))
    )
    (net (code "91") (name "unconnected-(U$4-3-SDA0-Pad3)") (class "Default")
      (node (ref "U$4") (pin "3") (pinfunction "3-SDA0_3") (pintype "bidirectional"))
    )
    (net (code "92") (name "unconnected-(U$4-4-DNC-Pad4)") (class "Default")
      (node (ref "U$4") (pin "4") (pinfunction "4-DNC_4") (pintype "bidirectional"))
    )
    (net (code "93") (name "unconnected-(U$4-5-SCL0-Pad5)") (class "Default")
      (node (ref "U$4") (pin "5") (pinfunction "5-SCL0_5") (pintype "bidirectional"))
    )
    (net (code "94") (name "unconnected-(U$4-6-GND-Pad6)") (class "Default")
      (node (ref "U$4") (pin "6") (pinfunction "6-GND_6") (pintype "bidirectional"))
    )
    (net (code "95") (name "unconnected-(U$4-7-GPIO7-Pad7)") (class "Default")
      (node (ref "U$4") (pin "7") (pinfunction "7-GPIO7_7") (pintype "bidirectional"))
    )
    (net (code "96") (name "unconnected-(U$4-8-TX-Pad8)") (class "Default")
      (node (ref "U$4") (pin "8") (pinfunction "8-TX_8") (pintype "bidirectional"))
    )
    (net (code "97") (name "unconnected-(U$4-9-DNC-Pad9)") (class "Default")
      (node (ref "U$4") (pin "9") (pinfunction "9-DNC_9") (pintype "bidirectional"))
    )
    (net (code "98") (name "unconnected-(U$4-10-RX-Pad10)") (class "Default")
      (node (ref "U$4") (pin "10") (pinfunction "10-RX_10") (pintype "bidirectional"))
    )
    (net (code "99") (name "unconnected-(U$4-11-GPIO0-Pad11)") (class "Default")
      (node (ref "U$4") (pin "11") (pinfunction "11-GPIO0_11") (pintype "bidirectional"))
    )
    (net (code "100") (name "unconnected-(U$4-12-GPIO1-Pad12)") (class "Default")
      (node (ref "U$4") (pin "12") (pinfunction "12-GPIO1_12") (pintype "bidirectional"))
    )
    (net (code "101") (name "unconnected-(U$4-13-GPIO2-Pad13)") (class "Default")
      (node (ref "U$4") (pin "13") (pinfunction "13-GPIO2_13") (pintype "bidirectional"))
    )
    (net (code "102") (name "unconnected-(U$4-14-DNC-Pad14)") (class "Default")
      (node (ref "U$4") (pin "14") (pinfunction "14-DNC_14") (pintype "bidirectional"))
    )
    (net (code "103") (name "unconnected-(U$4-15-GPIO3-Pad15)") (class "Default")
      (node (ref "U$4") (pin "15") (pinfunction "15-GPIO3_15") (pintype "bidirectional"))
    )
    (net (code "104") (name "unconnected-(U$4-16-GPIO4-Pad16)") (class "Default")
      (node (ref "U$4") (pin "16") (pinfunction "16-GPIO4_16") (pintype "bidirectional"))
    )
    (net (code "105") (name "unconnected-(U$4-17-DNC-Pad17)") (class "Default")
      (node (ref "U$4") (pin "17") (pinfunction "17-DNC_17") (pintype "bidirectional"))
    )
    (net (code "106") (name "unconnected-(U$4-18-GPIO5-Pad18)") (class "Default")
      (node (ref "U$4") (pin "18") (pinfunction "18-GPIO5_18") (pintype "bidirectional"))
    )
    (net (code "107") (name "unconnected-(U$4-19-SPI-MOSI-Pad19)") (class "Default")
      (node (ref "U$4") (pin "19") (pinfunction "19-SPI-MOSI_19") (pintype "bidirectional"))
    )
    (net (code "108") (name "unconnected-(U$4-20-DNC-Pad20)") (class "Default")
      (node (ref "U$4") (pin "20") (pinfunction "20-DNC_20") (pintype "bidirectional"))
    )
    (net (code "109") (name "unconnected-(U$4-21-SPI-MISO-Pad21)") (class "Default")
      (node (ref "U$4") (pin "21") (pinfunction "21-SPI-MISO_21") (pintype "bidirectional"))
    )
    (net (code "110") (name "unconnected-(U$4-22-GPIO6-Pad22)") (class "Default")
      (node (ref "U$4") (pin "22") (pinfunction "22-GPIO6_22") (pintype "bidirectional"))
    )
    (net (code "111") (name "unconnected-(U$4-23-SPI-SCLK-Pad23)") (class "Default")
      (node (ref "U$4") (pin "23") (pinfunction "23-SPI-SCLK_23") (pintype "bidirectional"))
    )
    (net (code "112") (name "unconnected-(U$4-24-SPI-CE0-N-Pad24)") (class "Default")
      (node (ref "U$4") (pin "24") (pinfunction "24-SPI-CE0-N_24") (pintype "bidirectional"))
    )
    (net (code "113") (name "unconnected-(U$4-25-DNC-Pad25)") (class "Default")
      (node (ref "U$4") (pin "25") (pinfunction "25-DNC_25") (pintype "bidirectional"))
    )
    (net (code "114") (name "unconnected-(U$4-26-SPI-CE1-N-Pad26)") (class "Default")
      (node (ref "U$4") (pin "26") (pinfunction "26-SPI-CE1-N_26") (pintype "bidirectional"))
    )
    (net (code "115") (name "unconnected-(U1-NC-Pad1)") (class "Default")
      (node (ref "U1") (pin "1") (pinfunction "NC_1") (pintype "no_connect"))
    )
    (net (code "116") (name "unconnected-(U1-NC-Pad6)") (class "Default")
      (node (ref "U1") (pin "6") (pinfunction "NC_6") (pintype "no_connect"))
    )
    (net (code "117") (name "unconnected-(U1-NC-Pad8)") (class "Default")
      (node (ref "U1") (pin "8") (pinfunction "NC_8") (pintype "no_connect"))
    )
    (net (code "118") (name "unconnected-(U2-NRESET-Pad16)") (class "Default")
      (node (ref "U2") (pin "16") (pinfunction "NRESET_16") (pintype "input"))
    )
    (net (code "119") (name "unconnected-(U2-SCL-Pad38)") (class "Default")
      (node (ref "U2") (pin "38") (pinfunction "SCL_38") (pintype "output"))
    )
    (net (code "120") (name "unconnected-(U2-SDA-Pad37)") (class "Default")
      (node (ref "U2") (pin "37") (pinfunction "SDA_37") (pintype "bidirectional"))
    )
    (net (code "121") (name "unconnected-(U2-SIM_PRESENCE-Pad34)") (class "Default")
      (node (ref "U2") (pin "34") (pinfunction "SIM_PRESENCE_34") (pintype "input"))
    )
    (net (code "122") (name "unconnected-(U3-AREF-Pad16)") (class "Default")
      (node (ref "U3") (pin "16") (pinfunction "AREF_16") (pintype "bidirectional"))
    )
    (net (code "123") (name "unconnected-(U3-GND-Pad33)") (class "Default")
      (node (ref "U3") (pin "33") (pinfunction "GND_33") (pintype "bidirectional"))
    )
    (net (code "124") (name "unconnected-(U3-MISO-Pad36)") (class "Default")
      (node (ref "U3") (pin "36") (pinfunction "MISO_36") (pintype "bidirectional"))
    )
    (net (code "125") (name "unconnected-(U3-MOSI-Pad32)") (class "Default")
      (node (ref "U3") (pin "32") (pinfunction "MOSI_32") (pintype "bidirectional"))
    )
    (net (code "126") (name "unconnected-(U3-PB2{slash}D10{slash}SS{slash}PWM-Pad11)") (class "Default")
      (node (ref "U3") (pin "11") (pinfunction "PB2/D10/SS/PWM_11") (pintype "bidirectional"))
    )
    (net (code "127") (name "unconnected-(U3-PB3{slash}D11{slash}MOSI{slash}PWM-Pad12)") (class "Default")
      (node (ref "U3") (pin "12") (pinfunction "PB3/D11/MOSI/PWM_12") (pintype "bidirectional"))
    )
    (net (code "128") (name "unconnected-(U3-PB4{slash}D12{slash}MISO-Pad13)") (class "Default")
      (node (ref "U3") (pin "13") (pinfunction "PB4/D12/MISO_13") (pintype "bidirectional"))
    )
    (net (code "129") (name "unconnected-(U3-PB5{slash}D13{slash}SCK-Pad14)") (class "Default")
      (node (ref "U3") (pin "14") (pinfunction "PB5/D13/SCK_14") (pintype "bidirectional"))
    )
    (net (code "130") (name "unconnected-(U3-PC0{slash}AD0{slash}D14-Pad17)") (class "Default")
      (node (ref "U3") (pin "17") (pinfunction "PC0/AD0/D14_17") (pintype "bidirectional"))
    )
    (net (code "131") (name "unconnected-(U3-PC1{slash}AD1{slash}D15-Pad18)") (class "Default")
      (node (ref "U3") (pin "18") (pinfunction "PC1/AD1/D15_18") (pintype "bidirectional"))
    )
    (net (code "132") (name "unconnected-(U3-PC2{slash}AD2{slash}D16-Pad19)") (class "Default")
      (node (ref "U3") (pin "19") (pinfunction "PC2/AD2/D16_19") (pintype "bidirectional"))
    )
    (net (code "133") (name "unconnected-(U3-PC3{slash}AD3{slash}D17-Pad20)") (class "Default")
      (node (ref "U3") (pin "20") (pinfunction "PC3/AD3/D17_20") (pintype "bidirectional"))
    )
    (net (code "134") (name "unconnected-(U3-PC4{slash}AD4{slash}D18{slash}SDA-Pad21)") (class "Default")
      (node (ref "U3") (pin "21") (pinfunction "PC4/AD4/D18/SDA_21") (pintype "bidirectional"))
    )
    (net (code "135") (name "unconnected-(U3-PC5{slash}AD5{slash}D19{slash}SCL-Pad22)") (class "Default")
      (node (ref "U3") (pin "22") (pinfunction "PC5/AD5/D19/SCL_22") (pintype "bidirectional"))
    )
    (net (code "136") (name "unconnected-(U3-PD2{slash}D2{slash}INT0-Pad3)") (class "Default")
      (node (ref "U3") (pin "3") (pinfunction "PD2/D2/INT0_3") (pintype "bidirectional"))
    )
    (net (code "137") (name "unconnected-(U3-PD3{slash}D3{slash}INT1{slash}PWM-Pad4)") (class "Default")
      (node (ref "U3") (pin "4") (pinfunction "PD3/D3/INT1/PWM_4") (pintype "bidirectional"))
    )
    (net (code "138") (name "unconnected-(U3-PD4{slash}D4-Pad5)") (class "Default")
      (node (ref "U3") (pin "5") (pinfunction "PD4/D4_5") (pintype "bidirectional"))
    )
    (net (code "139") (name "unconnected-(U3-PD5{slash}D5{slash}PWM-Pad6)") (class "Default")
      (node (ref "U3") (pin "6") (pinfunction "PD5/D5/PWM_6") (pintype "bidirectional"))
    )
    (net (code "140") (name "unconnected-(U3-PD6{slash}D6{slash}PWM-Pad7)") (class "Default")
      (node (ref "U3") (pin "7") (pinfunction "PD6/D6/PWM_7") (pintype "bidirectional"))
    )
    (net (code "141") (name "unconnected-(U3-RESET-Pad28)") (class "Default")
      (node (ref "U3") (pin "28") (pinfunction "RESET_28") (pintype "bidirectional"))
    )
    (net (code "142") (name "unconnected-(U3-RST-Pad34)") (class "Default")
      (node (ref "U3") (pin "34") (pinfunction "RST_34") (pintype "bidirectional"))
    )
    (net (code "143") (name "unconnected-(U3-SCK-Pad35)") (class "Default")
      (node (ref "U3") (pin "35") (pinfunction "SCK_35") (pintype "bidirectional"))
    )
    (net (code "144") (name "unconnected-(U3-VCC-Pad31)") (class "Default")
      (node (ref "U3") (pin "31") (pinfunction "VCC_31") (pintype "bidirectional"))
    )
  )
)
